# Thermostat_ADT6401_Breakout.net
KiCad netlist of a schematic drawn in EAGLE
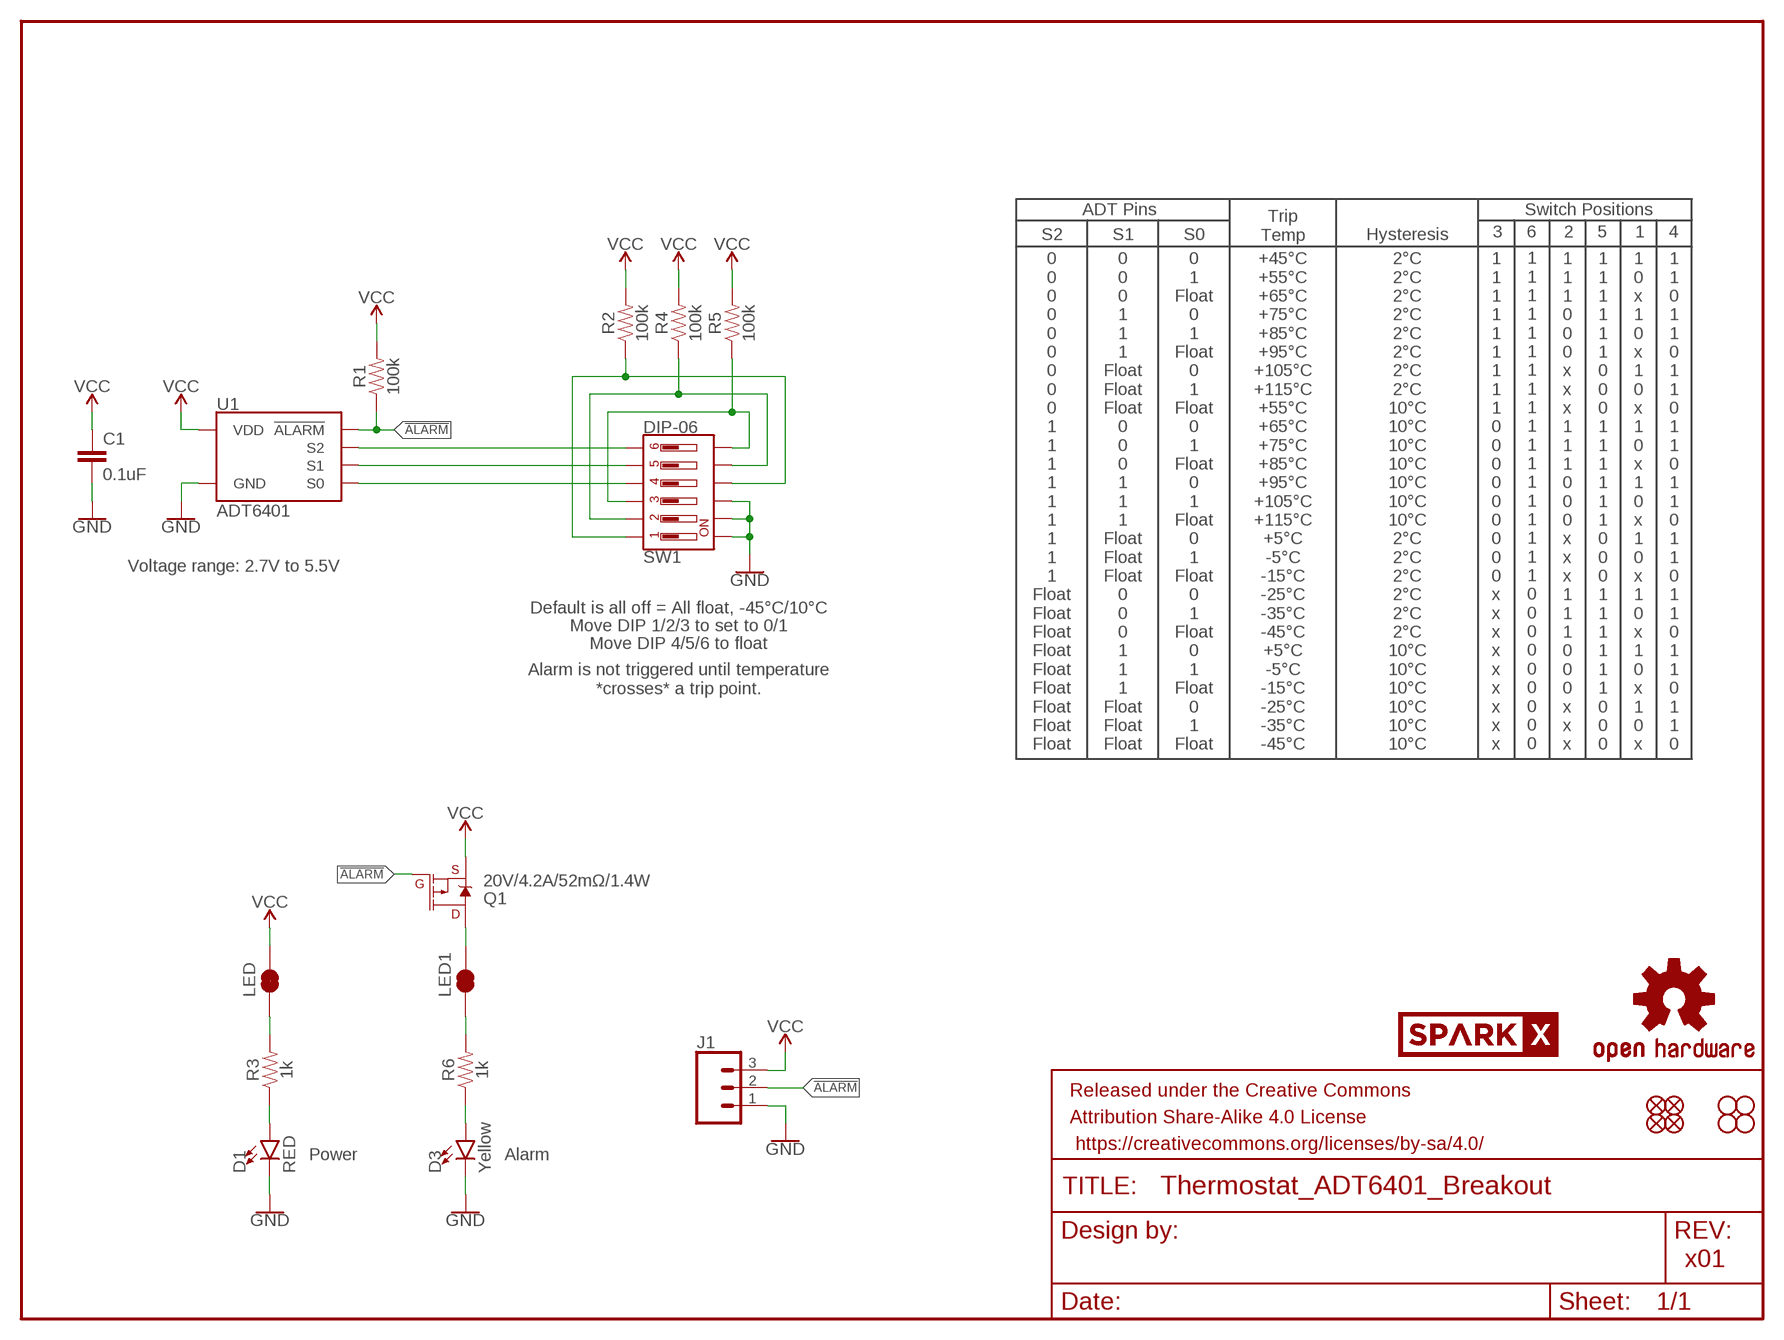
[diagram p0: schematic, sheet 1]

(export (version "E")
  (design (tool "Eeschema 10.0.6"))
  (components
    (comp (ref "C1")
      (value "0.1uF")
      (footprint "eagle-import:0603")
      (libsource (lib "eagle-import") (part "0.1UF-0603-25V-(+80/-20%)"))
    )
    (comp (ref "D1")
      (value "RED")
      (footprint "eagle-import:LED-0603")
      (libsource (lib "eagle-import") (part "LED-RED0603"))
    )
    (comp (ref "D3")
      (value "Yellow")
      (footprint "eagle-import:LED-0603")
      (libsource (lib "eagle-import") (part "LED-YELLOW0603"))
    )
    (comp (ref "FRAME1")
      (value "FRAME-LETTER")
      (footprint "eagle-import:CREATIVE_COMMONS")
      (libsource (lib "eagle-import") (part "FRAME-LETTER"))
    )
    (comp (ref "J1")
      (value "CONN_031X03_NO_SILK")
      (footprint "eagle-import:1X03_NO_SILK")
      (libsource (lib "eagle-import") (part "CONN_031X03_NO_SILK"))
    )
    (comp (ref "JP1")
      (value "FIDUCIAL1X2")
      (footprint "eagle-import:FIDUCIAL-1X2")
      (libsource (lib "eagle-import") (part "FIDUCIAL1X2"))
    )
    (comp (ref "JP2")
      (value "FIDUCIAL1X2")
      (footprint "eagle-import:FIDUCIAL-1X2")
      (libsource (lib "eagle-import") (part "FIDUCIAL1X2"))
    )
    (comp (ref "JP3")
      (value "STAND-OFF")
      (footprint "eagle-import:STAND-OFF")
      (libsource (lib "eagle-import") (part "STAND-OFF"))
    )
    (comp (ref "JP4")
      (value "STAND-OFF")
      (footprint "eagle-import:STAND-OFF")
      (libsource (lib "eagle-import") (part "STAND-OFF"))
    )
    (comp (ref "JP5")
      (value "FIDUCIAL1X2")
      (footprint "eagle-import:FIDUCIAL-1X2")
      (libsource (lib "eagle-import") (part "FIDUCIAL1X2"))
    )
    (comp (ref "JP6")
      (value "FIDUCIAL1X2")
      (footprint "eagle-import:FIDUCIAL-1X2")
      (libsource (lib "eagle-import") (part "FIDUCIAL1X2"))
    )
    (comp (ref "JP8")
      (value "STAND-OFF")
      (footprint "eagle-import:STAND-OFF")
      (libsource (lib "eagle-import") (part "STAND-OFF"))
    )
    (comp (ref "JP9")
      (value "STAND-OFF")
      (footprint "eagle-import:STAND-OFF")
      (libsource (lib "eagle-import") (part "STAND-OFF"))
    )
    (comp (ref "LED")
      (value "JUMPER-SMT_2_NC_TRACE_SILK")
      (footprint "eagle-import:SMT-JUMPER_2_NC_TRACE_SILK")
      (libsource (lib "eagle-import") (part "JUMPER-SMT_2_NC_TRACE_SILK"))
    )
    (comp (ref "LED1")
      (value "JUMPER-SMT_2_NC_TRACE_SILK")
      (footprint "eagle-import:SMT-JUMPER_2_NC_TRACE_SILK")
      (libsource (lib "eagle-import") (part "JUMPER-SMT_2_NC_TRACE_SILK"))
    )
    (comp (ref "LOGO1")
      (value "OSHW-LOGOMINI")
      (footprint "eagle-import:OSHW-LOGO-MINI")
      (libsource (lib "eagle-import") (part "OSHW-LOGOMINI"))
    )
    (comp (ref "Q1")
      (value "20V/4.2A/52mΩ/1.4W")
      (footprint "eagle-import:SOT23-3")
      (libsource (lib "eagle-import") (part "MOSFET_PCH-DMG2305UX-7"))
    )
    (comp (ref "R1")
      (value "100k")
      (footprint "eagle-import:0603")
      (libsource (lib "eagle-import") (part "100KOHM-0603-1/10W-1%"))
    )
    (comp (ref "R2")
      (value "100k")
      (footprint "eagle-import:0603")
      (libsource (lib "eagle-import") (part "100KOHM-0603-1/10W-1%"))
    )
    (comp (ref "R3")
      (value "1k")
      (footprint "eagle-import:0603")
      (libsource (lib "eagle-import") (part "1KOHM-0603-1/10W-1%"))
    )
    (comp (ref "R4")
      (value "100k")
      (footprint "eagle-import:0603")
      (libsource (lib "eagle-import") (part "100KOHM-0603-1/10W-1%"))
    )
    (comp (ref "R5")
      (value "100k")
      (footprint "eagle-import:0603")
      (libsource (lib "eagle-import") (part "100KOHM-0603-1/10W-1%"))
    )
    (comp (ref "R6")
      (value "1k")
      (footprint "eagle-import:0603")
      (libsource (lib "eagle-import") (part "1KOHM-0603-1/10W-1%"))
    )
    (comp (ref "SW1")
      (value "DIP-06")
      (footprint "eagle-import:DIPSWITCH-06-SMD")
      (libsource (lib "eagle-import") (part "DIP-06"))
    )
    (comp (ref "U$1")
      (value "SPARKX-LOGO4")
      (footprint "eagle-import:SPARKX-MEDIUM")
      (libsource (lib "eagle-import") (part "SPARKX-LOGO4"))
    )
    (comp (ref "U1")
      (value "ADT6401")
      (footprint "eagle-import:SOT23-6")
      (libsource (lib "eagle-import") (part "ADT6401"))
    )
  )
  (nets
    (net (code "1") (name "/~{ALARM}") (class "Default")
      (node (ref "J1") (pin "2") (pinfunction "2_2") (pintype "passive"))
      (node (ref "Q1") (pin "1") (pinfunction "G_1") (pintype "bidirectional"))
      (node (ref "R1") (pin "1") (pinfunction "1_1") (pintype "passive"))
      (node (ref "U1") (pin "6") (pinfunction "~{ALARM}_6") (pintype "bidirectional"))
    )
    (net (code "2") (name "GND") (class "Default")
      (node (ref "C1") (pin "2") (pinfunction "2_2") (pintype "passive"))
      (node (ref "D1") (pin "C") (pinfunction "C_C") (pintype "passive"))
      (node (ref "D3") (pin "C") (pinfunction "C_C") (pintype "passive"))
      (node (ref "J1") (pin "1") (pinfunction "1_1") (pintype "passive"))
      (node (ref "SW1") (pin "10") (pinfunction "10_10") (pintype "bidirectional"))
      (node (ref "SW1") (pin "11") (pinfunction "11_11") (pintype "bidirectional"))
      (node (ref "SW1") (pin "12") (pinfunction "12_12") (pintype "bidirectional"))
      (node (ref "U1") (pin "5") (pinfunction "GND_5") (pintype "power_in"))
    )
    (net (code "3") (name "Net-(D1-PadA)") (class "Default")
      (node (ref "D1") (pin "A") (pinfunction "A_A") (pintype "passive"))
      (node (ref "R3") (pin "1") (pinfunction "1_1") (pintype "passive"))
    )
    (net (code "4") (name "Net-(D3-PadA)") (class "Default")
      (node (ref "D3") (pin "A") (pinfunction "A_A") (pintype "passive"))
      (node (ref "R6") (pin "1") (pinfunction "1_1") (pintype "passive"))
    )
    (net (code "5") (name "Net-(LED-Pad1)") (class "Default")
      (node (ref "LED") (pin "1") (pinfunction "1_1") (pintype "passive"))
      (node (ref "R3") (pin "2") (pinfunction "2_2") (pintype "passive"))
    )
    (net (code "6") (name "Net-(LED1-Pad1)") (class "Default")
      (node (ref "LED1") (pin "1") (pinfunction "1_1") (pintype "passive"))
      (node (ref "R6") (pin "2") (pinfunction "2_2") (pintype "passive"))
    )
    (net (code "7") (name "Net-(Q1-D)") (class "Default")
      (node (ref "LED1") (pin "2") (pinfunction "2_2") (pintype "passive"))
      (node (ref "Q1") (pin "3") (pinfunction "D_3") (pintype "bidirectional"))
    )
    (net (code "8") (name "Net-(R2-Pad1)") (class "Default")
      (node (ref "R2") (pin "1") (pinfunction "1_1") (pintype "passive"))
      (node (ref "SW1") (pin "1") (pinfunction "1_1") (pintype "bidirectional"))
      (node (ref "SW1") (pin "9") (pinfunction "9_9") (pintype "bidirectional"))
    )
    (net (code "9") (name "Net-(R4-Pad1)") (class "Default")
      (node (ref "R4") (pin "1") (pinfunction "1_1") (pintype "passive"))
      (node (ref "SW1") (pin "2") (pinfunction "2_2") (pintype "bidirectional"))
      (node (ref "SW1") (pin "8") (pinfunction "8_8") (pintype "bidirectional"))
    )
    (net (code "10") (name "Net-(R5-Pad1)") (class "Default")
      (node (ref "R5") (pin "1") (pinfunction "1_1") (pintype "passive"))
      (node (ref "SW1") (pin "3") (pinfunction "3_3") (pintype "bidirectional"))
      (node (ref "SW1") (pin "7") (pinfunction "7_7") (pintype "bidirectional"))
    )
    (net (code "11") (name "Net-(U1-S0)") (class "Default")
      (node (ref "SW1") (pin "4") (pinfunction "4_4") (pintype "bidirectional"))
      (node (ref "U1") (pin "3") (pinfunction "S0_3") (pintype "input"))
    )
    (net (code "12") (name "Net-(U1-S1)") (class "Default")
      (node (ref "SW1") (pin "5") (pinfunction "5_5") (pintype "bidirectional"))
      (node (ref "U1") (pin "2") (pinfunction "S1_2") (pintype "bidirectional"))
    )
    (net (code "13") (name "Net-(U1-S2)") (class "Default")
      (node (ref "SW1") (pin "6") (pinfunction "6_6") (pintype "bidirectional"))
      (node (ref "U1") (pin "1") (pinfunction "S2_1") (pintype "bidirectional"))
    )
    (net (code "14") (name "VCC") (class "Default")
      (node (ref "C1") (pin "1") (pinfunction "1_1") (pintype "passive"))
      (node (ref "J1") (pin "3") (pinfunction "3_3") (pintype "passive"))
      (node (ref "LED") (pin "2") (pinfunction "2_2") (pintype "passive"))
      (node (ref "Q1") (pin "2") (pinfunction "S_2") (pintype "bidirectional"))
      (node (ref "R1") (pin "2") (pinfunction "2_2") (pintype "passive"))
      (node (ref "R2") (pin "2") (pinfunction "2_2") (pintype "passive"))
      (node (ref "R4") (pin "2") (pinfunction "2_2") (pintype "passive"))
      (node (ref "R5") (pin "2") (pinfunction "2_2") (pintype "passive"))
      (node (ref "U1") (pin "4") (pinfunction "VDD_4") (pintype "power_in"))
    )
  )
)
